# CFY01205V1_2.net
KiCad netlist of a schematic drawn in Altium Designer
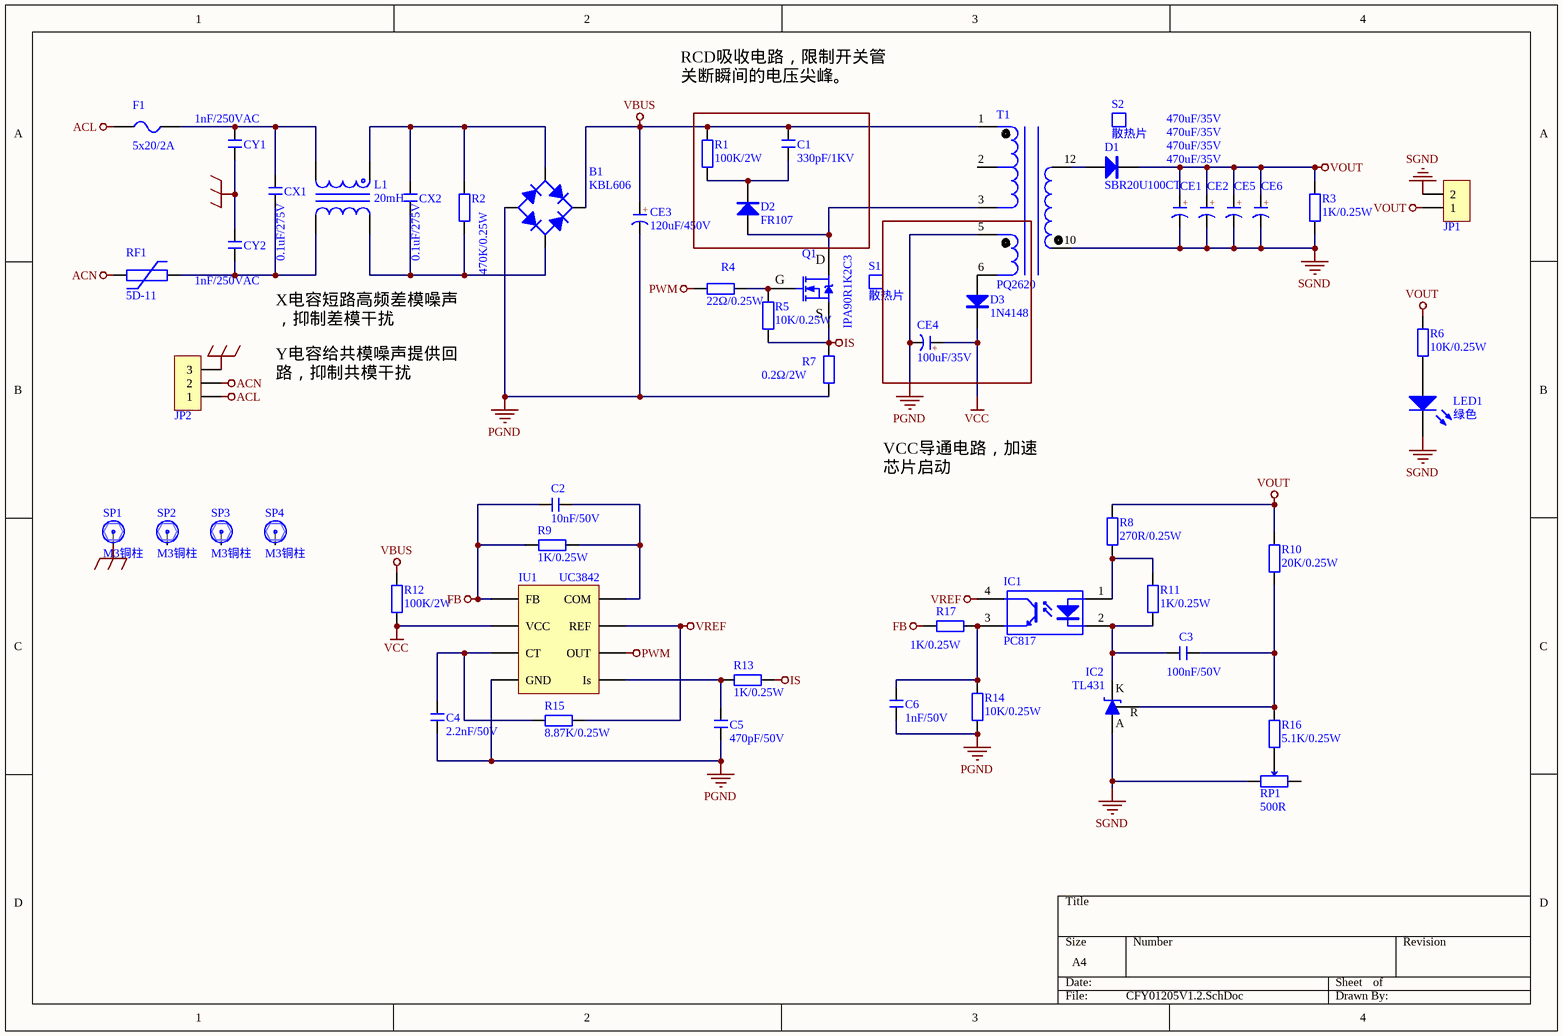
[diagram p0: CFY01205V1.2.SchDoc]

(export (version "E")
  (design (tool "Eeschema 10.0.6"))
  (components
    (comp (ref "B1")
      (value "KBL606")
      (footprint "KBL")
      (description "600V/8A整流桥")
      (fields (field (name "版权归属") "封装库来自淘宝卖家 ID：黄晶宝石"))
      (libsource (lib "0.2 - 二极管-整流桥") (part "KBL"))
    )
    (comp (ref "C1")
      (value "330pF/1KV")
      (footprint "CY 5*7*2.5")
      (description "瓷片电容")
      (libsource (lib "0.1 - 电阻-电容-电感") (part "CC"))
    )
    (comp (ref "C2")
      (value "10nF/50V")
      (footprint "CC 2*5")
      (description "瓷片电容")
      (libsource (lib "0.1 - 电阻-电容-电感") (part "CC"))
    )
    (comp (ref "C3")
      (value "100nF/50V")
      (footprint "CC 2*5")
      (description "瓷片电容")
      (libsource (lib "0.1 - 电阻-电容-电感") (part "CC"))
    )
    (comp (ref "C4")
      (value "2.2nF/50V")
      (footprint "CC 2*5")
      (description "瓷片电容")
      (libsource (lib "0.1 - 电阻-电容-电感") (part "CC"))
    )
    (comp (ref "C5")
      (value "470pF/50V")
      (footprint "CC 2*5")
      (description "瓷片电容")
      (libsource (lib "0.1 - 电阻-电容-电感") (part "CC"))
    )
    (comp (ref "C6")
      (value "1nF/50V")
      (footprint "CC 2*5")
      (description "瓷片电容")
      (libsource (lib "0.1 - 电阻-电容-电感") (part "CC"))
    )
    (comp (ref "CE1")
      (value "470uF/35V")
      (footprint "CAP 5.0*10*12.5")
      (description "直插电解电容")
      (libsource (lib "0.1 - 电阻-电容-电感") (part "CE"))
    )
    (comp (ref "CE2")
      (value "470uF/35V")
      (footprint "CAP 5.0*10*12.5")
      (description "直插电解电容")
      (libsource (lib "0.1 - 电阻-电容-电感") (part "CE"))
    )
    (comp (ref "CE3")
      (value "120uF/450V")
      (footprint "CAP 7.5*18*35.5")
      (description "直插电解电容")
      (libsource (lib "0.1 - 电阻-电容-电感") (part "CE"))
    )
    (comp (ref "CE4")
      (value "100uF/35V")
      (footprint "CAP 2.5*6.3*11.2")
      (description "直插电解电容")
      (libsource (lib "") (part "CE_1"))
    )
    (comp (ref "CE5")
      (value "470uF/35V")
      (footprint "CAP 5.0*10*12.5")
      (description "直插电解电容")
      (libsource (lib "0.1 - 电阻-电容-电感") (part "CE"))
    )
    (comp (ref "CE6")
      (value "470uF/35V")
      (footprint "CAP 5.0*10*12.5")
      (description "直插电解电容")
      (libsource (lib "0.1 - 电阻-电容-电感") (part "CE"))
    )
    (comp (ref "CX1")
      (value "0.1uF/275V")
      (footprint "CX 10-13*11")
      (description "安规X电容")
      (fields (field (name "版权归属") "封装库来自淘宝 ID：黄晶宝石"))
      (libsource (lib "0.1 - 电阻-电容-电感") (part "CX"))
    )
    (comp (ref "CX2")
      (value "0.1uF/275V")
      (footprint "CX 10-13*11")
      (description "安规X电容")
      (fields (field (name "版权归属") "封装库来自淘宝 ID：黄晶宝石"))
      (libsource (lib "0.1 - 电阻-电容-电感") (part "CX"))
    )
    (comp (ref "CY1")
      (value "1nF/250VAC")
      (footprint "CY 7.5*8*4")
      (description "安规Y电容")
      (fields (field (name "版权归属") "封装库来自淘宝 ID：黄晶宝石"))
      (libsource (lib "0.1 - 电阻-电容-电感") (part "CY"))
    )
    (comp (ref "CY2")
      (value "1nF/250VAC")
      (footprint "CY 7.5*8*4")
      (description "安规Y电容")
      (fields (field (name "版权归属") "封装库来自淘宝 ID：黄晶宝石"))
      (libsource (lib "0.1 - 电阻-电容-电感") (part "CY"))
    )
    (comp (ref "D1")
      (value "SBR20U100CT")
      (footprint "TO220A")
      (description "整流二极管")
      (libsource (lib "0.2 - 二极管-整流桥") (part "1N4007"))
    )
    (comp (ref "D2")
      (value "FR107")
      (footprint "DO-41")
      (description "整流二极管")
      (libsource (lib "0.2 - 二极管-整流桥") (part "1N4007"))
    )
    (comp (ref "D3")
      (value "1N4148")
      (footprint "DO-35")
      (description "整流二极管")
      (libsource (lib "0.2 - 二极管-整流桥") (part "1N4007"))
    )
    (comp (ref "F1")
      (value "5x20/2A")
      (footprint "FU 4x16_V")
      (description "直插保险丝")
      (fields (field (name "版权归属") "封装库来自淘宝卖家 ID：黄晶宝石"))
      (libsource (lib "2.0 - 保险丝-晶振-光耦") (part "FU DIP"))
    )
    (comp (ref "IC1")
      (value "PC817")
      (footprint "DIP4-300")
      (description "线性光耦")
      (fields (field (name "版权归属") "封装库来自淘宝 ID：黄晶宝石"))
      (libsource (lib "1.2 - 传感元件") (part "817"))
    )
    (comp (ref "IC2")
      (value "TL431")
      (footprint "TO92A")
      (description "可调基准稳压芯片")
      (fields (field (name "版权归属") "封装库来自淘宝 ID：黄晶宝石"))
      (libsource (lib "1.1 - 电源类芯片") (part "TL431-ID"))
    )
    (comp (ref "IU1")
      (value "UC3842")
      (footprint "DIP8-300")
      (libsource (lib "1.7 - MAX系列芯片") (part "UC3842"))
    )
    (comp (ref "JP1")
      (value "HDR-1X2")
      (footprint "KF7620-2P")
      (description "2P接插件")
      (fields (field (name "版权归属") "封装库来自淘宝 ID：黄晶宝石"))
      (libsource (lib "6.2 - 接插件-脚距7.62 (300mil) ") (part "Header 2"))
    )
    (comp (ref "JP2")
      (value "HDR-1X3")
      (footprint "KF7620-3P")
      (description "3P接插件")
      (fields (field (name "版权归属") "封装库来自淘宝 ID：黄晶宝石"))
      (libsource (lib "6.2 - 接插件-脚距7.62 (300mil) ") (part "Header 3"))
    )
    (comp (ref "L1")
      (value "20mH")
      (footprint "UU10.5")
      (description "共模电感")
      (fields (field (name "版权归属") "封装库来自淘宝 ID：黄晶宝石"))
      (libsource (lib "0.1 - 电阻-电容-电感") (part "L-UU"))
    )
    (comp (ref "LED1")
      (value "绿色")
      (footprint "LED 3MM-G")
      (description "直插3mm LED")
      (fields (field (name "版权归属") "封装库来自淘宝 ID：黄晶宝石"))
      (libsource (lib "0.3 - LED发光二极管") (part "LED-3MM"))
    )
    (comp (ref "Q1")
      (value "IPA90R1K2C3")
      (footprint "TO220A")
      (description "N沟场效应管")
      (libsource (lib "0.5 - 场效应管-可控硅") (part "IRF840"))
    )
    (comp (ref "R1")
      (value "100K/2W")
      (footprint "RS 2W-V6")
      (description "色环电阻")
      (fields (field (name "版权归属") "封装库来自淘宝 ID：黄晶宝石"))
      (libsource (lib "0.1 - 电阻-电容-电感") (part "R-S"))
    )
    (comp (ref "R2")
      (value "470K/0.25W")
      (footprint "RS 1/4W")
      (description "色环电阻")
      (fields (field (name "版权归属") "封装库来自淘宝 ID：黄晶宝石"))
      (libsource (lib "0.1 - 电阻-电容-电感") (part "R-S"))
    )
    (comp (ref "R3")
      (value "1K/0.25W")
      (footprint "RS 1/4W")
      (description "色环电阻")
      (fields (field (name "版权归属") "封装库来自淘宝 ID：黄晶宝石"))
      (libsource (lib "0.1 - 电阻-电容-电感") (part "R-S"))
    )
    (comp (ref "R4")
      (value "22Ω/0.25W")
      (footprint "RS 1/4W")
      (description "色环电阻")
      (fields (field (name "版权归属") "封装库来自淘宝 ID：黄晶宝石"))
      (libsource (lib "0.1 - 电阻-电容-电感") (part "R-S"))
    )
    (comp (ref "R5")
      (value "10K/0.25W")
      (footprint "RS 1/4W")
      (description "色环电阻")
      (fields (field (name "版权归属") "封装库来自淘宝 ID：黄晶宝石"))
      (libsource (lib "0.1 - 电阻-电容-电感") (part "R-S"))
    )
    (comp (ref "R6")
      (value "10K/0.25W")
      (footprint "RS 1/4W")
      (description "色环电阻")
      (fields (field (name "版权归属") "封装库来自淘宝 ID：黄晶宝石"))
      (libsource (lib "0.1 - 电阻-电容-电感") (part "R-S"))
    )
    (comp (ref "R7")
      (value "0.2Ω/2W")
      (footprint "RS 2W-V6")
      (description "色环电阻")
      (fields (field (name "版权归属") "封装库来自淘宝 ID：黄晶宝石"))
      (libsource (lib "0.1 - 电阻-电容-电感") (part "R-S"))
    )
    (comp (ref "R8")
      (value "270R/0.25W")
      (footprint "RS 1/4W")
      (description "色环电阻")
      (fields (field (name "版权归属") "封装库来自淘宝 ID：黄晶宝石"))
      (libsource (lib "0.1 - 电阻-电容-电感") (part "R-S"))
    )
    (comp (ref "R9")
      (value "1K/0.25W")
      (footprint "RS 1/4W")
      (description "色环电阻")
      (fields (field (name "版权归属") "封装库来自淘宝 ID：黄晶宝石"))
      (libsource (lib "0.1 - 电阻-电容-电感") (part "R-S"))
    )
    (comp (ref "R10")
      (value "20K/0.25W")
      (footprint "RS 1/4W")
      (description "色环电阻")
      (fields (field (name "版权归属") "封装库来自淘宝 ID：黄晶宝石"))
      (libsource (lib "0.1 - 电阻-电容-电感") (part "R-S"))
    )
    (comp (ref "R11")
      (value "1K/0.25W")
      (footprint "RS 1/4W")
      (description "色环电阻")
      (fields (field (name "版权归属") "封装库来自淘宝 ID：黄晶宝石"))
      (libsource (lib "0.1 - 电阻-电容-电感") (part "R-S"))
    )
    (comp (ref "R12")
      (value "100K/2W")
      (footprint "RS 2W-V6")
      (description "色环电阻")
      (fields (field (name "版权归属") "封装库来自淘宝 ID：黄晶宝石"))
      (libsource (lib "0.1 - 电阻-电容-电感") (part "R-S"))
    )
    (comp (ref "R13")
      (value "1K/0.25W")
      (footprint "RS 1/4W")
      (description "色环电阻")
      (fields (field (name "版权归属") "封装库来自淘宝 ID：黄晶宝石"))
      (libsource (lib "0.1 - 电阻-电容-电感") (part "R-S"))
    )
    (comp (ref "R14")
      (value "10K/0.25W")
      (footprint "RS 1/4W")
      (description "色环电阻")
      (fields (field (name "版权归属") "封装库来自淘宝 ID：黄晶宝石"))
      (libsource (lib "0.1 - 电阻-电容-电感") (part "R-S"))
    )
    (comp (ref "R15")
      (value "8.87K/0.25W")
      (footprint "RS 1/4W")
      (description "色环电阻")
      (fields (field (name "版权归属") "封装库来自淘宝 ID：黄晶宝石"))
      (libsource (lib "0.1 - 电阻-电容-电感") (part "R-S"))
    )
    (comp (ref "R16")
      (value "5.1K/0.25W")
      (footprint "RS 1/4W")
      (description "色环电阻")
      (fields (field (name "版权归属") "封装库来自淘宝 ID：黄晶宝石"))
      (libsource (lib "0.1 - 电阻-电容-电感") (part "R-S"))
    )
    (comp (ref "R17")
      (value "1K/0.25W")
      (footprint "RS 1/4W")
      (description "色环电阻")
      (fields (field (name "版权归属") "封装库来自淘宝 ID：黄晶宝石"))
      (libsource (lib "0.1 - 电阻-电容-电感") (part "R-S"))
    )
    (comp (ref "RF1")
      (value "5D-11")
      (footprint "TVR-10D")
      (description "PPTC自恢复保险丝")
      (fields (field (name "版权归属") "封装库来自淘宝卖家 ID：黄晶宝石"))
      (libsource (lib "2.0 - 保险丝-晶振-光耦") (part "PPTC"))
    )
    (comp (ref "RP1")
      (value "500R")
      (footprint "3296W")
      (description "单联电位器")
      (fields (field (name "版权归属") "封装库来自淘宝 ID：黄晶宝石"))
      (libsource (lib "0.1 - 电阻-电容-电感") (part "RP"))
    )
    (comp (ref "S1")
      (value "散热片")
      (footprint "SRP16-24-25-P")
      (fields (field (name "版权归属") "封装库来自淘宝 ID：黄晶宝石"))
      (libsource (lib "4.1 - 未分类器件") (part "S1"))
    )
    (comp (ref "S2")
      (value "散热片")
      (footprint "SRP16-24-25-P")
      (fields (field (name "版权归属") "封装库来自淘宝 ID：黄晶宝石"))
      (libsource (lib "4.1 - 未分类器件") (part "S1"))
    )
    (comp (ref "SP1")
      (value "M3铜柱")
      (footprint "M3x4+6_N")
      (description "铜柱")
      (fields (field (name "版权归属") "封装库来自淘宝 ID：黄晶宝石"))
      (libsource (lib "4.1 - 未分类器件") (part "铜柱加头大焊盘"))
    )
    (comp (ref "SP2")
      (value "M3铜柱")
      (footprint "M3x4+6_N")
      (description "铜柱")
      (fields (field (name "版权归属") "封装库来自淘宝 ID：黄晶宝石"))
      (libsource (lib "4.1 - 未分类器件") (part "铜柱加头大焊盘"))
    )
    (comp (ref "SP3")
      (value "M3铜柱")
      (footprint "M3x4+6_N")
      (description "铜柱")
      (fields (field (name "版权归属") "封装库来自淘宝 ID：黄晶宝石"))
      (libsource (lib "4.1 - 未分类器件") (part "铜柱加头大焊盘"))
    )
    (comp (ref "SP4")
      (value "M3铜柱")
      (footprint "M3x4+6_N")
      (description "铜柱")
      (fields (field (name "版权归属") "封装库来自淘宝 ID：黄晶宝石"))
      (libsource (lib "4.1 - 未分类器件") (part "铜柱加头大焊盘"))
    )
    (comp (ref "T1")
      (value "PQ2620")
      (footprint "PQ2625+6PIN")
      (description "12V 高频变压器")
      (fields (field (name "版权归属") "https://shop463601444.taobao.com"))
      (libsource (lib "CFY01202") (part "PQ2620"))
    )
  )
  (nets
    (net (code "1") (name "ACL") (class "Default")
      (node (ref "F1") (pin "2") (pinfunction "2_2") (pintype "passive"))
      (node (ref "JP2") (pin "1") (pinfunction "1_1") (pintype "passive"))
    )
    (net (code "2") (name "ACN") (class "Default")
      (node (ref "JP2") (pin "2") (pinfunction "2_2") (pintype "passive"))
      (node (ref "RF1") (pin "1") (pinfunction "1_1") (pintype "passive"))
    )
    (net (code "3") (name "FB") (class "Default")
      (node (ref "C2") (pin "1") (pinfunction "1_1") (pintype "passive"))
      (node (ref "IU1") (pin "2") (pinfunction "FB_2") (pintype "passive"))
      (node (ref "R17") (pin "1") (pinfunction "1_1") (pintype "passive"))
      (node (ref "R9") (pin "2") (pinfunction "2_2") (pintype "passive"))
    )
    (net (code "4") (name "IS") (class "Default")
      (node (ref "Q1") (pin "3") (pinfunction "S_3") (pintype "passive"))
      (node (ref "R13") (pin "1") (pinfunction "1_1") (pintype "passive"))
      (node (ref "R5") (pin "1") (pinfunction "1_1") (pintype "passive"))
      (node (ref "R7") (pin "2") (pinfunction "2_2") (pintype "passive"))
    )
    (net (code "5") (name "Net-(B1-PadAC1)") (class "Default")
      (node (ref "B1") (pin "AC1") (pinfunction "AC1_AC1") (pintype "passive"))
      (node (ref "CX2") (pin "2") (pinfunction "2_2") (pintype "passive"))
      (node (ref "L1") (pin "1") (pinfunction "1_1") (pintype "passive"))
      (node (ref "R2") (pin "1") (pinfunction "1_1") (pintype "passive"))
    )
    (net (code "6") (name "Net-(B1-PadAC2)") (class "Default")
      (node (ref "B1") (pin "AC2") (pinfunction "AC2_AC2") (pintype "passive"))
      (node (ref "CX2") (pin "1") (pinfunction "1_1") (pintype "passive"))
      (node (ref "L1") (pin "4") (pinfunction "4_4") (pintype "passive"))
      (node (ref "R2") (pin "2") (pinfunction "2_2") (pintype "passive"))
    )
    (net (code "7") (name "Net-(CX1-Pad1)") (class "Default")
      (node (ref "CX1") (pin "1") (pinfunction "1_1") (pintype "passive"))
      (node (ref "CY2") (pin "1") (pinfunction "1_1") (pintype "passive"))
      (node (ref "L1") (pin "3") (pinfunction "3_3") (pintype "passive"))
      (node (ref "RF1") (pin "2") (pinfunction "2_2") (pintype "passive"))
    )
    (net (code "8") (name "Net-(CX1-Pad2)") (class "Default")
      (node (ref "CX1") (pin "2") (pinfunction "2_2") (pintype "passive"))
      (node (ref "CY1") (pin "2") (pinfunction "2_2") (pintype "passive"))
      (node (ref "F1") (pin "1") (pinfunction "1_1") (pintype "passive"))
      (node (ref "L1") (pin "2") (pinfunction "2_2") (pintype "passive"))
    )
    (net (code "9") (name "Net-(D1-A)") (class "Default")
      (node (ref "D1") (pin "1") (pinfunction "A_1") (pintype "passive"))
      (node (ref "T1") (pin "12") (pinfunction "12_12") (pintype "passive"))
    )
    (net (code "10") (name "Net-(D2-A)") (class "Default")
      (node (ref "D2") (pin "1") (pinfunction "A_1") (pintype "passive"))
      (node (ref "Q1") (pin "2") (pinfunction "D_2") (pintype "passive"))
      (node (ref "T1") (pin "3") (pinfunction "3_3") (pintype "passive"))
    )
    (net (code "11") (name "Net-(D2-K)") (class "Default")
      (node (ref "C1") (pin "2") (pinfunction "2_2") (pintype "passive"))
      (node (ref "D2") (pin "2") (pinfunction "K_2") (pintype "passive"))
      (node (ref "R1") (pin "1") (pinfunction "1_1") (pintype "passive"))
    )
    (net (code "12") (name "Net-(D3-A)") (class "Default")
      (node (ref "D3") (pin "1") (pinfunction "A_1") (pintype "passive"))
      (node (ref "T1") (pin "6") (pinfunction "6_6") (pintype "passive"))
    )
    (net (code "13") (name "Net-(IC1-A)") (class "Default")
      (node (ref "IC1") (pin "1") (pinfunction "A_1") (pintype "passive"))
      (node (ref "R11") (pin "1") (pinfunction "1_1") (pintype "passive"))
      (node (ref "R8") (pin "2") (pinfunction "2_2") (pintype "passive"))
    )
    (net (code "14") (name "Net-(IC1-E)") (class "Default")
      (node (ref "C6") (pin "2") (pinfunction "2_2") (pintype "passive"))
      (node (ref "IC1") (pin "3") (pinfunction "E_3") (pintype "passive"))
      (node (ref "R14") (pin "1") (pinfunction "1_1") (pintype "passive"))
      (node (ref "R17") (pin "2") (pinfunction "2_2") (pintype "passive"))
    )
    (net (code "15") (name "Net-(IC1-K)") (class "Default")
      (node (ref "C3") (pin "1") (pinfunction "1_1") (pintype "passive"))
      (node (ref "IC1") (pin "2") (pinfunction "K_2") (pintype "passive"))
      (node (ref "IC2") (pin "3") (pinfunction "K_3") (pintype "passive"))
      (node (ref "R11") (pin "2") (pinfunction "2_2") (pintype "passive"))
    )
    (net (code "16") (name "Net-(IC2-R)") (class "Default")
      (node (ref "C3") (pin "2") (pinfunction "2_2") (pintype "passive"))
      (node (ref "IC2") (pin "1") (pinfunction "R_1") (pintype "passive"))
      (node (ref "R10") (pin "2") (pinfunction "2_2") (pintype "passive"))
      (node (ref "R16") (pin "1") (pinfunction "1_1") (pintype "passive"))
    )
    (net (code "17") (name "Net-(IU1-COM)") (class "Default")
      (node (ref "C2") (pin "2") (pinfunction "2_2") (pintype "passive"))
      (node (ref "IU1") (pin "1") (pinfunction "COM_1") (pintype "passive"))
      (node (ref "R9") (pin "1") (pinfunction "1_1") (pintype "passive"))
    )
    (net (code "18") (name "Net-(IU1-CT)") (class "Default")
      (node (ref "C4") (pin "1") (pinfunction "1_1") (pintype "passive"))
      (node (ref "IU1") (pin "4") (pinfunction "CT_4") (pintype "passive"))
      (node (ref "R15") (pin "1") (pinfunction "1_1") (pintype "passive"))
    )
    (net (code "19") (name "Net-(IU1-Is)") (class "Default")
      (node (ref "C5") (pin "1") (pinfunction "1_1") (pintype "passive"))
      (node (ref "IU1") (pin "3") (pinfunction "Is_3") (pintype "passive"))
      (node (ref "R13") (pin "2") (pinfunction "2_2") (pintype "passive"))
    )
    (net (code "20") (name "Net-(LED1-A)") (class "Default")
      (node (ref "LED1") (pin "1") (pinfunction "A_1") (pintype "passive"))
      (node (ref "R6") (pin "1") (pinfunction "1_1") (pintype "passive"))
    )
    (net (code "21") (name "Net-(Q1-G)") (class "Default")
      (node (ref "Q1") (pin "1") (pinfunction "G_1") (pintype "passive"))
      (node (ref "R4") (pin "1") (pinfunction "1_1") (pintype "passive"))
      (node (ref "R5") (pin "2") (pinfunction "2_2") (pintype "passive"))
    )
    (net (code "22") (name "Net-(R16-Pad2)") (class "Default")
      (node (ref "R16") (pin "2") (pinfunction "2_2") (pintype "passive"))
      (node (ref "RP1") (pin "2") (pinfunction "2_2") (pintype "passive"))
    )
    (net (code "23") (name "PE") (class "Default")
      (node (ref "CY1") (pin "1") (pinfunction "1_1") (pintype "passive"))
      (node (ref "CY2") (pin "2") (pinfunction "2_2") (pintype "passive"))
      (node (ref "JP2") (pin "3") (pinfunction "3_3") (pintype "passive"))
      (node (ref "SP1") (pin "1") (pinfunction "1_1") (pintype "passive"))
    )
    (net (code "24") (name "PGND") (class "Default")
      (node (ref "B1") (pin "DC-") (pinfunction "DC-_DC-") (pintype "passive"))
      (node (ref "C4") (pin "2") (pinfunction "2_2") (pintype "passive"))
      (node (ref "C5") (pin "2") (pinfunction "2_2") (pintype "passive"))
      (node (ref "C6") (pin "1") (pinfunction "1_1") (pintype "passive"))
      (node (ref "CE3") (pin "2") (pinfunction "K_2") (pintype "passive"))
      (node (ref "CE4") (pin "2") (pinfunction "K_2") (pintype "passive"))
      (node (ref "IU1") (pin "5") (pinfunction "GND_5") (pintype "passive"))
      (node (ref "R14") (pin "2") (pinfunction "2_2") (pintype "passive"))
      (node (ref "R7") (pin "1") (pinfunction "1_1") (pintype "passive"))
      (node (ref "T1") (pin "5") (pinfunction "5_5") (pintype "passive"))
    )
    (net (code "25") (name "PWM") (class "Default")
      (node (ref "IU1") (pin "6") (pinfunction "OUT_6") (pintype "passive"))
      (node (ref "R4") (pin "2") (pinfunction "2_2") (pintype "passive"))
    )
    (net (code "26") (name "SGND") (class "Default")
      (node (ref "CE1") (pin "2") (pinfunction "K_2") (pintype "passive"))
      (node (ref "CE2") (pin "2") (pinfunction "K_2") (pintype "passive"))
      (node (ref "CE5") (pin "2") (pinfunction "K_2") (pintype "passive"))
      (node (ref "CE6") (pin "2") (pinfunction "K_2") (pintype "passive"))
      (node (ref "IC2") (pin "2") (pinfunction "A_2") (pintype "passive"))
      (node (ref "JP1") (pin "2") (pinfunction "2_2") (pintype "passive"))
      (node (ref "LED1") (pin "2") (pinfunction "K_2") (pintype "passive"))
      (node (ref "R3") (pin "2") (pinfunction "2_2") (pintype "passive"))
      (node (ref "RP1") (pin "1") (pinfunction "1_1") (pintype "passive"))
      (node (ref "T1") (pin "10") (pinfunction "10_10") (pintype "passive"))
    )
    (net (code "27") (name "VBUS") (class "Default")
      (node (ref "B1") (pin "DC+") (pinfunction "DC+_DC+") (pintype "passive"))
      (node (ref "C1") (pin "1") (pinfunction "1_1") (pintype "passive"))
      (node (ref "CE3") (pin "1") (pinfunction "A_1") (pintype "passive"))
      (node (ref "R1") (pin "2") (pinfunction "2_2") (pintype "passive"))
      (node (ref "R12") (pin "1") (pinfunction "1_1") (pintype "passive"))
      (node (ref "T1") (pin "1") (pinfunction "1_1") (pintype "passive"))
    )
    (net (code "28") (name "VCC") (class "Default")
      (node (ref "CE4") (pin "1") (pinfunction "A_1") (pintype "passive"))
      (node (ref "D3") (pin "2") (pinfunction "K_2") (pintype "passive"))
      (node (ref "IU1") (pin "7") (pinfunction "VCC_7") (pintype "passive"))
      (node (ref "R12") (pin "2") (pinfunction "2_2") (pintype "passive"))
    )
    (net (code "29") (name "VOUT") (class "Default")
      (node (ref "CE1") (pin "1") (pinfunction "A_1") (pintype "passive"))
      (node (ref "CE2") (pin "1") (pinfunction "A_1") (pintype "passive"))
      (node (ref "CE5") (pin "1") (pinfunction "A_1") (pintype "passive"))
      (node (ref "CE6") (pin "1") (pinfunction "A_1") (pintype "passive"))
      (node (ref "D1") (pin "2") (pinfunction "K_2") (pintype "passive"))
      (node (ref "JP1") (pin "1") (pinfunction "1_1") (pintype "passive"))
      (node (ref "R10") (pin "1") (pinfunction "1_1") (pintype "passive"))
      (node (ref "R3") (pin "1") (pinfunction "1_1") (pintype "passive"))
      (node (ref "R6") (pin "2") (pinfunction "2_2") (pintype "passive"))
      (node (ref "R8") (pin "1") (pinfunction "1_1") (pintype "passive"))
    )
    (net (code "30") (name "VREF") (class "Default")
      (node (ref "IC1") (pin "4") (pinfunction "C_4") (pintype "passive"))
      (node (ref "IU1") (pin "8") (pinfunction "REF_8") (pintype "passive"))
      (node (ref "R15") (pin "2") (pinfunction "2_2") (pintype "passive"))
    )
    (net (code "31") (name "unconnected-(RP1-Pad3)") (class "Default")
      (node (ref "RP1") (pin "3") (pinfunction "3_3") (pintype "passive"))
    )
    (net (code "32") (name "unconnected-(SP2-Pad1)") (class "Default")
      (node (ref "SP2") (pin "1") (pinfunction "1_1") (pintype "passive"))
    )
    (net (code "33") (name "unconnected-(SP3-Pad1)") (class "Default")
      (node (ref "SP3") (pin "1") (pinfunction "1_1") (pintype "passive"))
    )
    (net (code "34") (name "unconnected-(SP4-Pad1)") (class "Default")
      (node (ref "SP4") (pin "1") (pinfunction "1_1") (pintype "passive"))
    )
    (net (code "35") (name "unconnected-(T1-Pad2)") (class "Default")
      (node (ref "T1") (pin "2") (pinfunction "2_2") (pintype "passive"))
    )
  )
)
